# schematic.net
KiCad netlist of a schematic drawn in EasyEDA
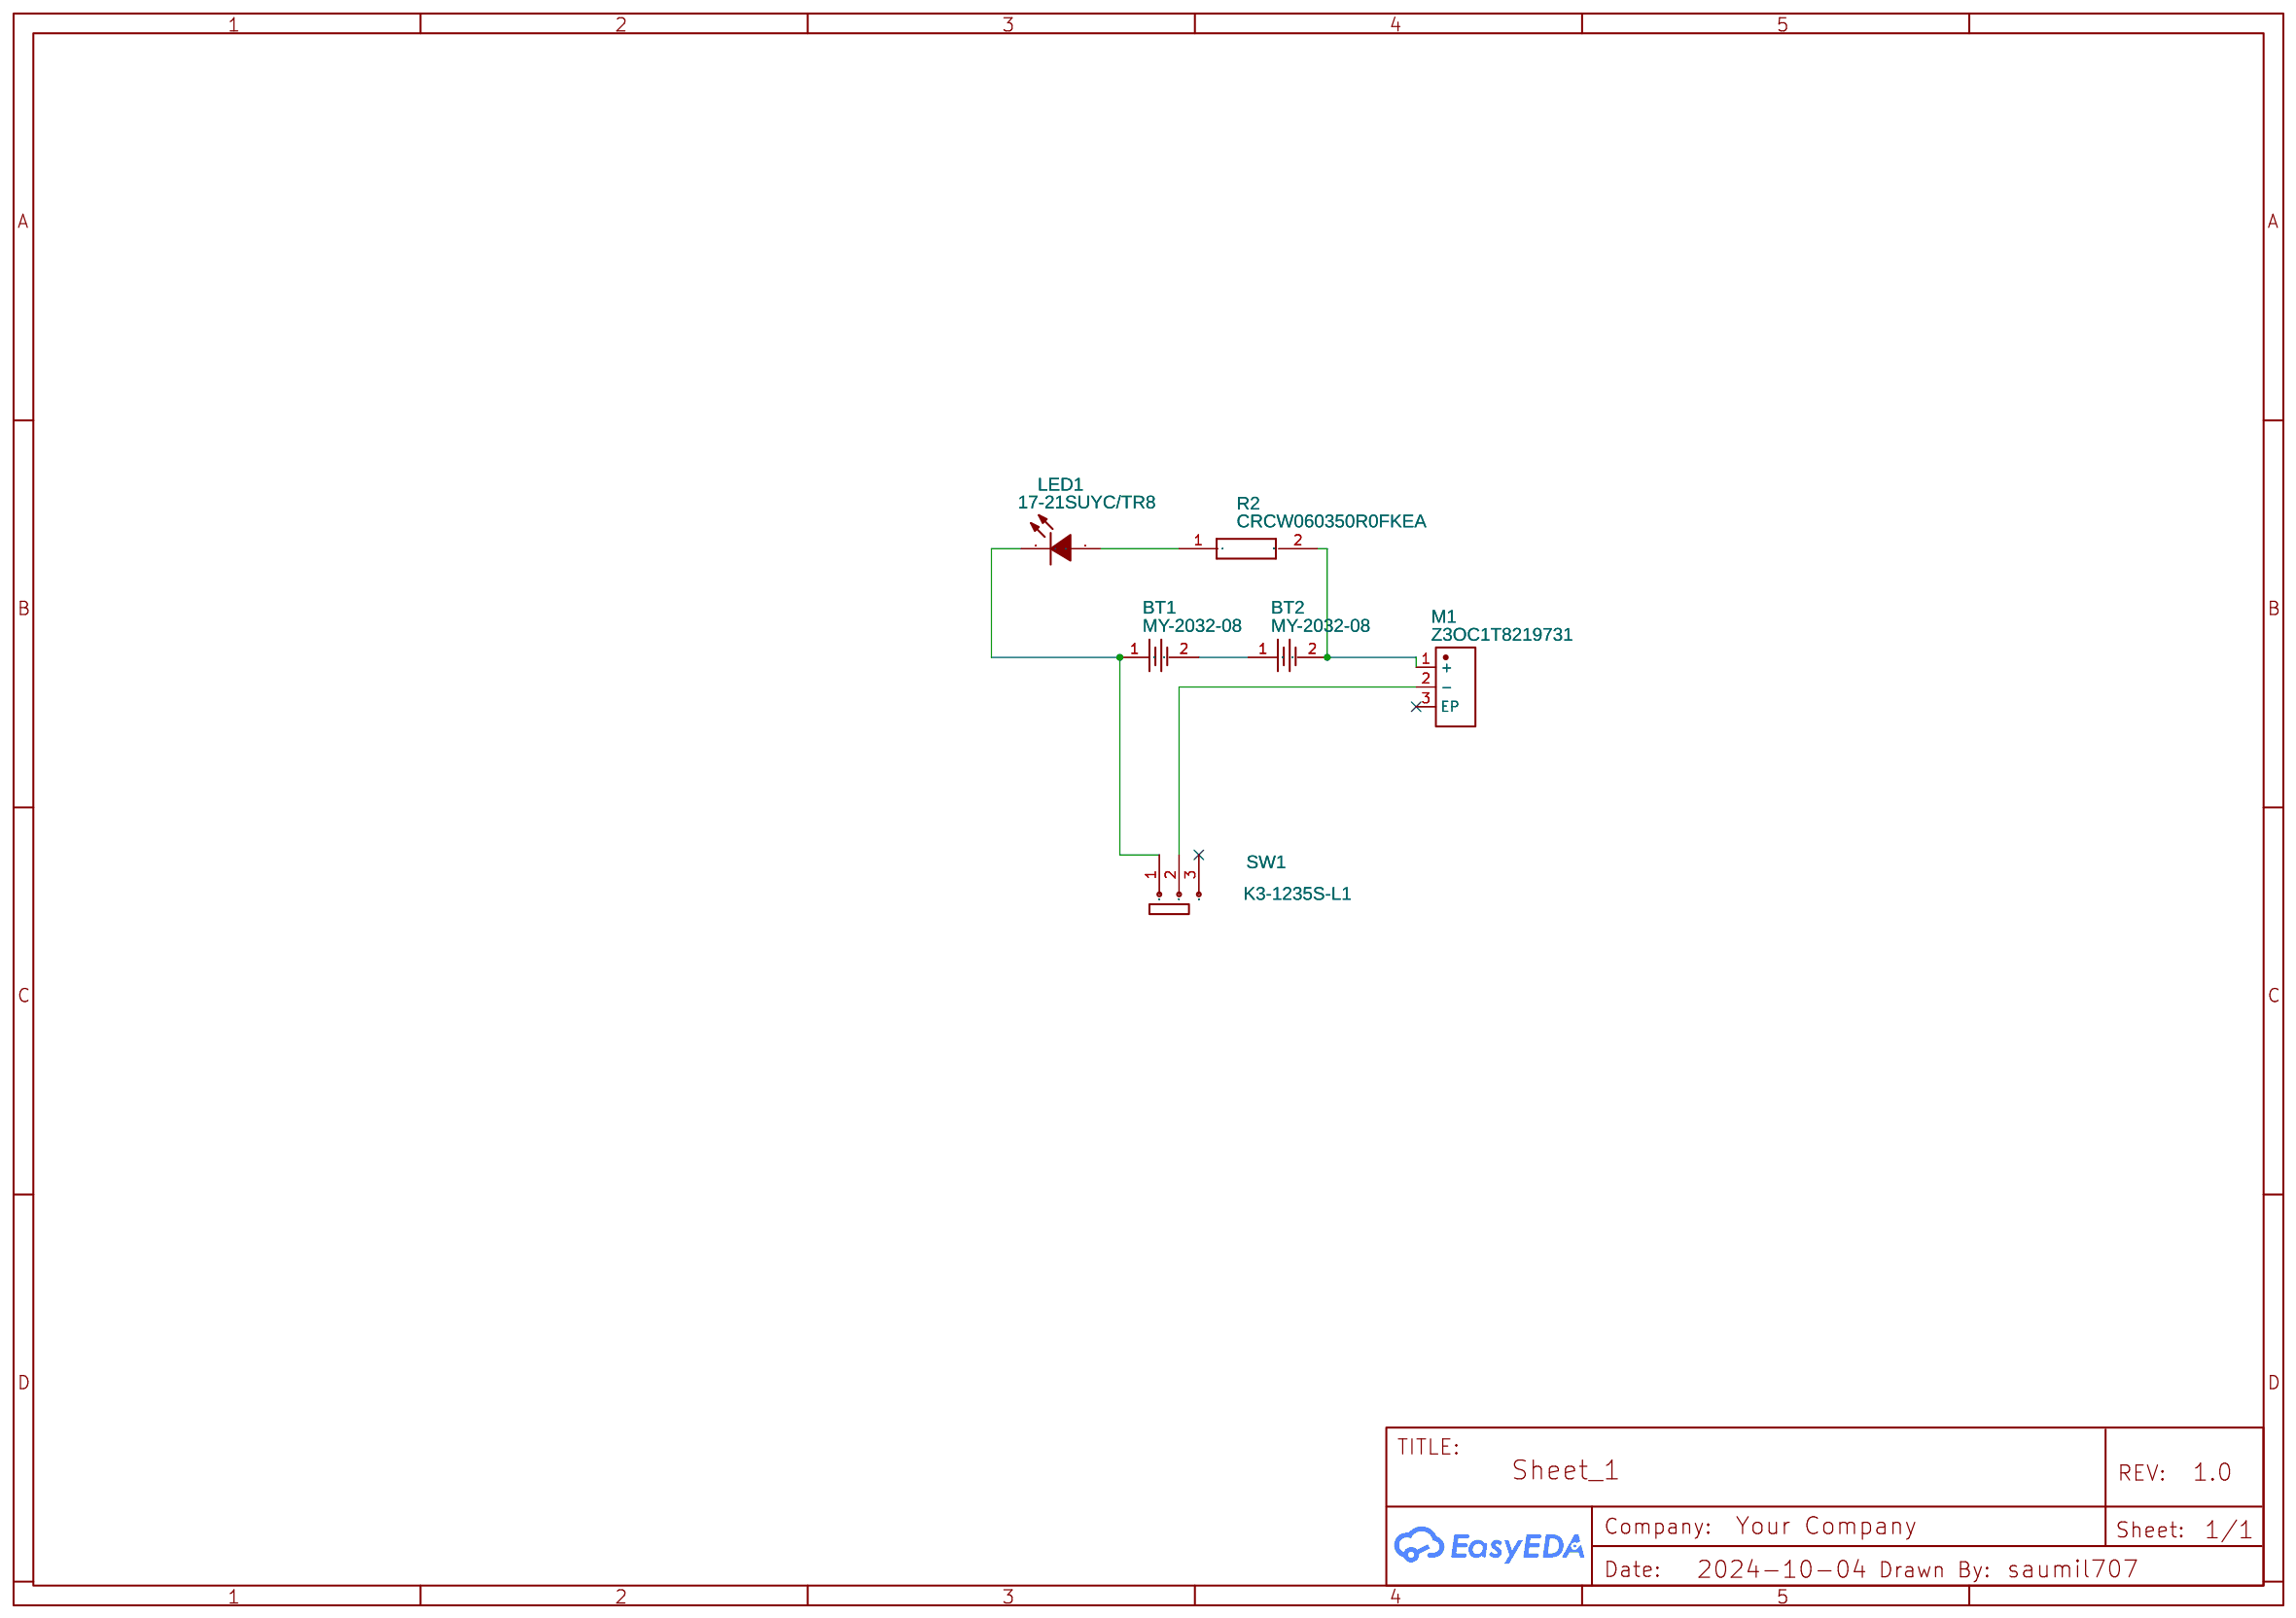
[diagram p0: schematic sheet]

(export (version "E")
  (design (tool "Eeschema 10.0.6"))
  (components
    (comp (ref "BT1")
      (value "MY-2032-08")
      (fields (field (name "Manufacturer") "MYOUNG(美阳)"))
      (libsource (lib "") (part "MY-2032-08"))
    )
    (comp (ref "BT2")
      (value "MY-2032-08")
      (fields (field (name "Manufacturer") "MYOUNG(美阳)"))
      (libsource (lib "") (part "MY-2032-08"))
    )
    (comp (ref "LED1")
      (value "17-21SUYC/TR8")
      (fields (field (name "Manufacturer Part") "KT-0805黄灯") (field (name "Manufacturer") "KENTO"))
      (libsource (lib "") (part "17-21SUYC/TR8"))
    )
    (comp (ref "M1")
      (value "Z3OC1T8219731")
      (fields (field (name "Manufacturer") "KOTL(金龙机电)"))
      (libsource (lib "") (part "Z3OC1T8219731"))
    )
    (comp (ref "R2") (value "CRCW060350R0FKEA") (libsource (lib "") (part "CRCW060350R0FKEA")))
    (comp (ref "SW1")
      (value "K3-1235S-L1")
      (fields (field (name "Manufacturer") "韩国韩荣"))
      (libsource (lib "") (part "K3-1235S-L1"))
    )
  )
  (nets
    (net (code "1") (name "Net-(BT1-Pad2)") (class "Default")
      (node (ref "BT1") (pin "2") (pinfunction "2_2") (pintype "input"))
      (node (ref "BT2") (pin "1") (pinfunction "1_1") (pintype "input"))
    )
    (net (code "2") (name "Net-(LED1-+)") (class "Default")
      (node (ref "LED1") (pin "1") (pinfunction "+_1") (pintype "unspecified"))
      (node (ref "R2") (pin "1") (pinfunction "1_1") (pintype "bidirectional"))
    )
    (net (code "3") (name "Net-(LED1--)") (class "Default")
      (node (ref "BT1") (pin "1") (pinfunction "1_1") (pintype "input"))
      (node (ref "LED1") (pin "2") (pinfunction "-_2") (pintype "unspecified"))
      (node (ref "SW1") (pin "1") (pinfunction "1_1") (pintype "unspecified"))
    )
    (net (code "4") (name "Net-(M1-+)") (class "Default")
      (node (ref "BT2") (pin "2") (pinfunction "2_2") (pintype "input"))
      (node (ref "M1") (pin "1") (pinfunction "+_1") (pintype "unspecified"))
      (node (ref "R2") (pin "2") (pinfunction "2_2") (pintype "bidirectional"))
    )
    (net (code "5") (name "Net-(M1--)") (class "Default")
      (node (ref "M1") (pin "2") (pinfunction "-_2") (pintype "unspecified"))
      (node (ref "SW1") (pin "2") (pinfunction "2_2") (pintype "unspecified"))
    )
    (net (code "6") (name "unconnected-(M1-EP-Pad3)") (class "Default")
      (node (ref "M1") (pin "3") (pinfunction "EP_3") (pintype "unspecified+no_connect"))
    )
    (net (code "7") (name "unconnected-(SW1-Pad3)") (class "Default")
      (node (ref "SW1") (pin "3") (pinfunction "3_3") (pintype "unspecified+no_connect"))
    )
  )
)
